# Adafruit_LIS3DH.net
KiCad netlist of a schematic drawn in EAGLE
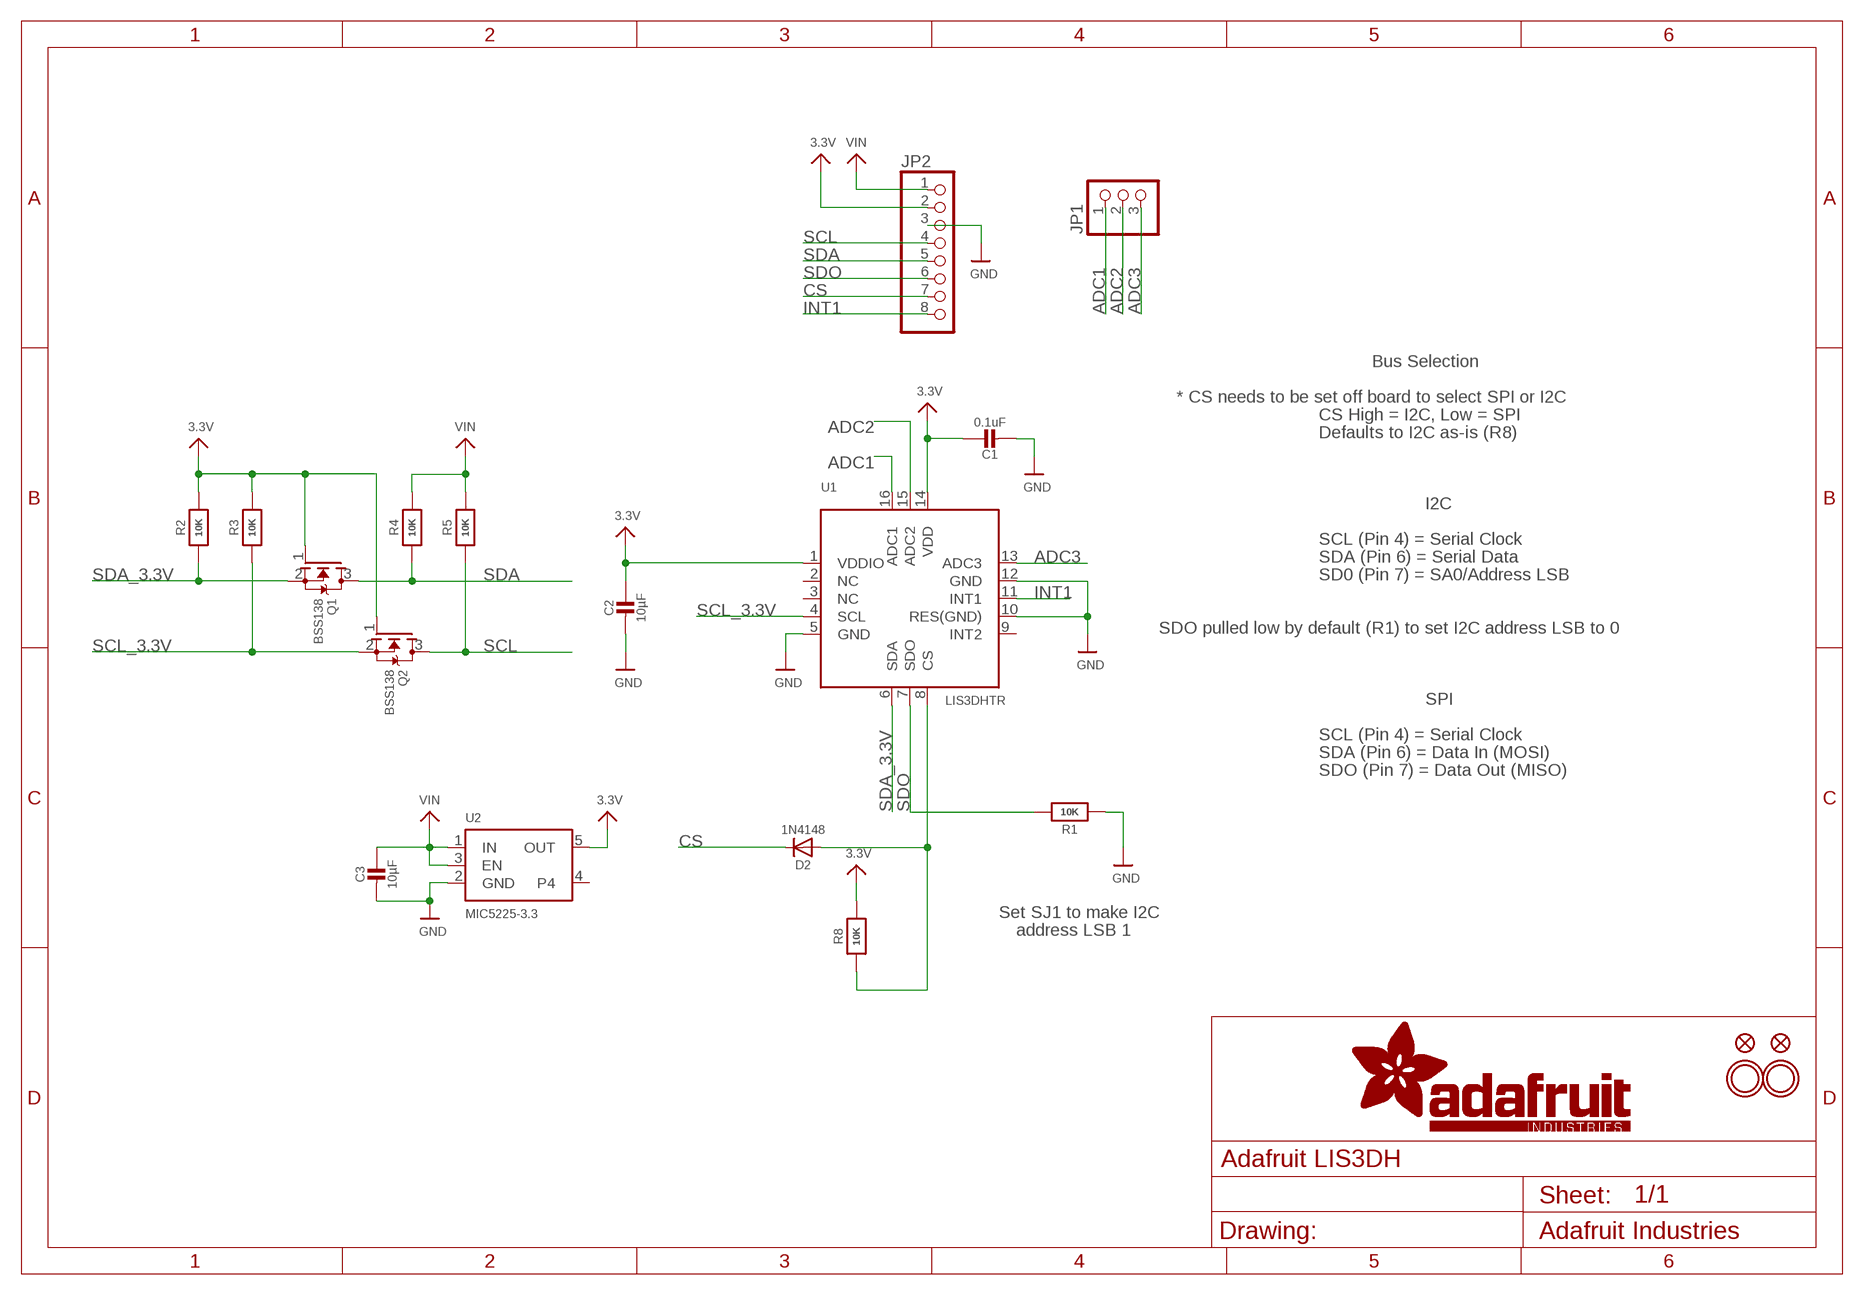
[diagram p0: schematic, sheet 1]

(export (version "E")
  (design (tool "Eeschema 10.0.6"))
  (components
    (comp (ref "C1")
      (value "0.1uF")
      (footprint "eagle-import:0805_10MGAP")
      (libsource (lib "eagle-import") (part "CAP_CERAMIC0805_10MGAP"))
    )
    (comp (ref "C2")
      (value "10µF")
      (footprint "eagle-import:0805-NO")
      (libsource (lib "eagle-import") (part "CAP_CERAMIC0805-NOOUTLINE"))
    )
    (comp (ref "C3")
      (value "10µF")
      (footprint "eagle-import:0805-NO")
      (libsource (lib "eagle-import") (part "CAP_CERAMIC0805-NOOUTLINE"))
    )
    (comp (ref "D2")
      (value "1N4148")
      (footprint "eagle-import:SOD-323")
      (libsource (lib "eagle-import") (part "DIODESOD-323"))
    )
    (comp (ref "FID1")
      (value "FIDUCIAL\"\"")
      (footprint "eagle-import:FIDUCIAL_1MM")
      (libsource (lib "eagle-import") (part "FIDUCIAL{dblquote}{dblquote}"))
    )
    (comp (ref "FID2")
      (value "FIDUCIAL\"\"")
      (footprint "eagle-import:FIDUCIAL_1MM")
      (libsource (lib "eagle-import") (part "FIDUCIAL{dblquote}{dblquote}"))
    )
    (comp (ref "JP1")
      (value "HEADER-1X3ROUND")
      (footprint "eagle-import:1X03_ROUND")
      (libsource (lib "eagle-import") (part "HEADER-1X3ROUND"))
    )
    (comp (ref "JP2")
      (value "HEADER-1X870MIL")
      (footprint "eagle-import:1X08_ROUND_70")
      (libsource (lib "eagle-import") (part "HEADER-1X870MIL"))
    )
    (comp (ref "Q1")
      (value "BSS138")
      (footprint "eagle-import:SOT23-WIDE")
      (libsource (lib "eagle-import") (part "MOSFET-NWIDE"))
    )
    (comp (ref "Q2")
      (value "BSS138")
      (footprint "eagle-import:SOT23-WIDE")
      (libsource (lib "eagle-import") (part "MOSFET-NWIDE"))
    )
    (comp (ref "R1")
      (value "10K")
      (footprint "eagle-import:0805-NO")
      (libsource (lib "eagle-import") (part "RESISTOR0805_NOOUTLINE"))
    )
    (comp (ref "R2")
      (value "10K")
      (footprint "eagle-import:0805-NO")
      (libsource (lib "eagle-import") (part "RESISTOR0805_NOOUTLINE"))
    )
    (comp (ref "R3")
      (value "10K")
      (footprint "eagle-import:0805-NO")
      (libsource (lib "eagle-import") (part "RESISTOR0805_NOOUTLINE"))
    )
    (comp (ref "R4")
      (value "10K")
      (footprint "eagle-import:0805-NO")
      (libsource (lib "eagle-import") (part "RESISTOR0805_NOOUTLINE"))
    )
    (comp (ref "R5")
      (value "10K")
      (footprint "eagle-import:0805-NO")
      (libsource (lib "eagle-import") (part "RESISTOR0805_NOOUTLINE"))
    )
    (comp (ref "R8")
      (value "10K")
      (footprint "eagle-import:0805-NO")
      (libsource (lib "eagle-import") (part "RESISTOR0805_NOOUTLINE"))
    )
    (comp (ref "U$10")
      (value "MOUNTINGHOLE2.5")
      (footprint "eagle-import:MOUNTINGHOLE_2.5_PLATED")
      (libsource (lib "eagle-import") (part "MOUNTINGHOLE2.5"))
    )
    (comp (ref "U$13")
      (value "MOUNTINGHOLE2.5")
      (footprint "eagle-import:MOUNTINGHOLE_2.5_PLATED")
      (libsource (lib "eagle-import") (part "MOUNTINGHOLE2.5"))
    )
    (comp (ref "U1")
      (value "LIS3DHTR")
      (footprint "eagle-import:LGA16_3X3MM")
      (libsource (lib "eagle-import") (part "ACCEL_LIS3DHTR"))
    )
    (comp (ref "U2")
      (value "MIC5225-3.3")
      (footprint "eagle-import:SOT23-5")
      (libsource (lib "eagle-import") (part "VREG_SOT23-5"))
    )
  )
  (nets
    (net (code "1") (name "/ADC1") (class "Default")
      (node (ref "JP1") (pin "1") (pinfunction "1_1") (pintype "passive"))
      (node (ref "U1") (pin "16") (pinfunction "ADC1_16") (pintype "input"))
    )
    (net (code "2") (name "/ADC2") (class "Default")
      (node (ref "JP1") (pin "2") (pinfunction "2_2") (pintype "passive"))
      (node (ref "U1") (pin "15") (pinfunction "ADC2_15") (pintype "input"))
    )
    (net (code "3") (name "/ADC3") (class "Default")
      (node (ref "JP1") (pin "3") (pinfunction "3_3") (pintype "passive"))
      (node (ref "U1") (pin "13") (pinfunction "ADC3_13") (pintype "input"))
    )
    (net (code "4") (name "/CS") (class "Default")
      (node (ref "D2") (pin "C") (pinfunction "C_C") (pintype "passive"))
      (node (ref "JP2") (pin "7") (pinfunction "7_7") (pintype "passive"))
    )
    (net (code "5") (name "/INT1") (class "Default")
      (node (ref "JP2") (pin "8") (pinfunction "8_8") (pintype "passive"))
      (node (ref "U1") (pin "11") (pinfunction "INT1_11") (pintype "output"))
    )
    (net (code "6") (name "/SCL") (class "Default")
      (node (ref "JP2") (pin "4") (pinfunction "4_4") (pintype "passive"))
      (node (ref "Q2") (pin "3") (pinfunction "D_3") (pintype "bidirectional"))
      (node (ref "R5") (pin "1") (pinfunction "1_1") (pintype "passive"))
    )
    (net (code "7") (name "/SCL_3.3V") (class "Default")
      (node (ref "Q2") (pin "2") (pinfunction "S_2") (pintype "bidirectional"))
      (node (ref "R3") (pin "1") (pinfunction "1_1") (pintype "passive"))
      (node (ref "U1") (pin "4") (pinfunction "SCL_4") (pintype "bidirectional"))
    )
    (net (code "8") (name "/SDA") (class "Default")
      (node (ref "JP2") (pin "5") (pinfunction "5_5") (pintype "passive"))
      (node (ref "Q1") (pin "3") (pinfunction "D_3") (pintype "bidirectional"))
      (node (ref "R4") (pin "1") (pinfunction "1_1") (pintype "passive"))
    )
    (net (code "9") (name "/SDA_3.3V") (class "Default")
      (node (ref "Q1") (pin "2") (pinfunction "S_2") (pintype "bidirectional"))
      (node (ref "R2") (pin "1") (pinfunction "1_1") (pintype "passive"))
      (node (ref "U1") (pin "6") (pinfunction "SDA_6") (pintype "bidirectional"))
    )
    (net (code "10") (name "/SDO") (class "Default")
      (node (ref "JP2") (pin "6") (pinfunction "6_6") (pintype "passive"))
      (node (ref "R1") (pin "2") (pinfunction "2_2") (pintype "passive"))
      (node (ref "U1") (pin "7") (pinfunction "SDO_7") (pintype "bidirectional"))
    )
    (net (code "11") (name "3.3V") (class "Default")
      (node (ref "C1") (pin "1") (pinfunction "1_1") (pintype "passive"))
      (node (ref "C2") (pin "1") (pinfunction "1_1") (pintype "passive"))
      (node (ref "JP2") (pin "2") (pinfunction "2_2") (pintype "passive"))
      (node (ref "Q1") (pin "1") (pinfunction "G_1") (pintype "bidirectional"))
      (node (ref "Q2") (pin "1") (pinfunction "G_1") (pintype "bidirectional"))
      (node (ref "R2") (pin "2") (pinfunction "2_2") (pintype "passive"))
      (node (ref "R3") (pin "2") (pinfunction "2_2") (pintype "passive"))
      (node (ref "R8") (pin "2") (pinfunction "2_2") (pintype "passive"))
      (node (ref "U1") (pin "1") (pinfunction "VDDIO_1") (pintype "power_in"))
      (node (ref "U1") (pin "14") (pinfunction "VDD_14") (pintype "power_in"))
      (node (ref "U2") (pin "5") (pinfunction "OUT_5") (pintype "power_in"))
    )
    (net (code "12") (name "GND") (class "Default")
      (node (ref "C1") (pin "2") (pinfunction "2_2") (pintype "passive"))
      (node (ref "C2") (pin "2") (pinfunction "2_2") (pintype "passive"))
      (node (ref "C3") (pin "2") (pinfunction "2_2") (pintype "passive"))
      (node (ref "JP2") (pin "3") (pinfunction "3_3") (pintype "passive"))
      (node (ref "R1") (pin "1") (pinfunction "1_1") (pintype "passive"))
      (node (ref "U1") (pin "10") (pinfunction "RES(GND)_10") (pintype "bidirectional"))
      (node (ref "U1") (pin "12") (pinfunction "GND_12") (pintype "power_in"))
      (node (ref "U1") (pin "5") (pinfunction "GND_5") (pintype "power_in"))
      (node (ref "U2") (pin "2") (pinfunction "GND_2") (pintype "power_in"))
    )
    (net (code "13") (name "Net-(U1-CS)") (class "Default")
      (node (ref "D2") (pin "A") (pinfunction "A_A") (pintype "passive"))
      (node (ref "R8") (pin "1") (pinfunction "1_1") (pintype "passive"))
      (node (ref "U1") (pin "8") (pinfunction "CS_8") (pintype "input"))
    )
    (net (code "14") (name "VIN") (class "Default")
      (node (ref "C3") (pin "1") (pinfunction "1_1") (pintype "passive"))
      (node (ref "JP2") (pin "1") (pinfunction "1_1") (pintype "passive"))
      (node (ref "R4") (pin "2") (pinfunction "2_2") (pintype "passive"))
      (node (ref "R5") (pin "2") (pinfunction "2_2") (pintype "passive"))
      (node (ref "U2") (pin "1") (pinfunction "IN_1") (pintype "power_in"))
      (node (ref "U2") (pin "3") (pinfunction "EN_3") (pintype "input"))
    )
    (net (code "15") (name "unconnected-(U1-INT2-Pad9)") (class "Default")
      (node (ref "U1") (pin "9") (pinfunction "INT2_9") (pintype "output"))
    )
    (net (code "16") (name "unconnected-(U1-NC-Pad2)") (class "Default")
      (node (ref "U1") (pin "2") (pinfunction "NC_2") (pintype "no_connect"))
    )
    (net (code "17") (name "unconnected-(U1-NC-Pad3)") (class "Default")
      (node (ref "U1") (pin "3") (pinfunction "NC_3") (pintype "no_connect"))
    )
    (net (code "18") (name "unconnected-(U2-P4-Pad4)") (class "Default")
      (node (ref "U2") (pin "4") (pinfunction "P4_4") (pintype "bidirectional"))
    )
  )
)
